# ds1804.net
KiCad netlist of a schematic drawn in EAGLE
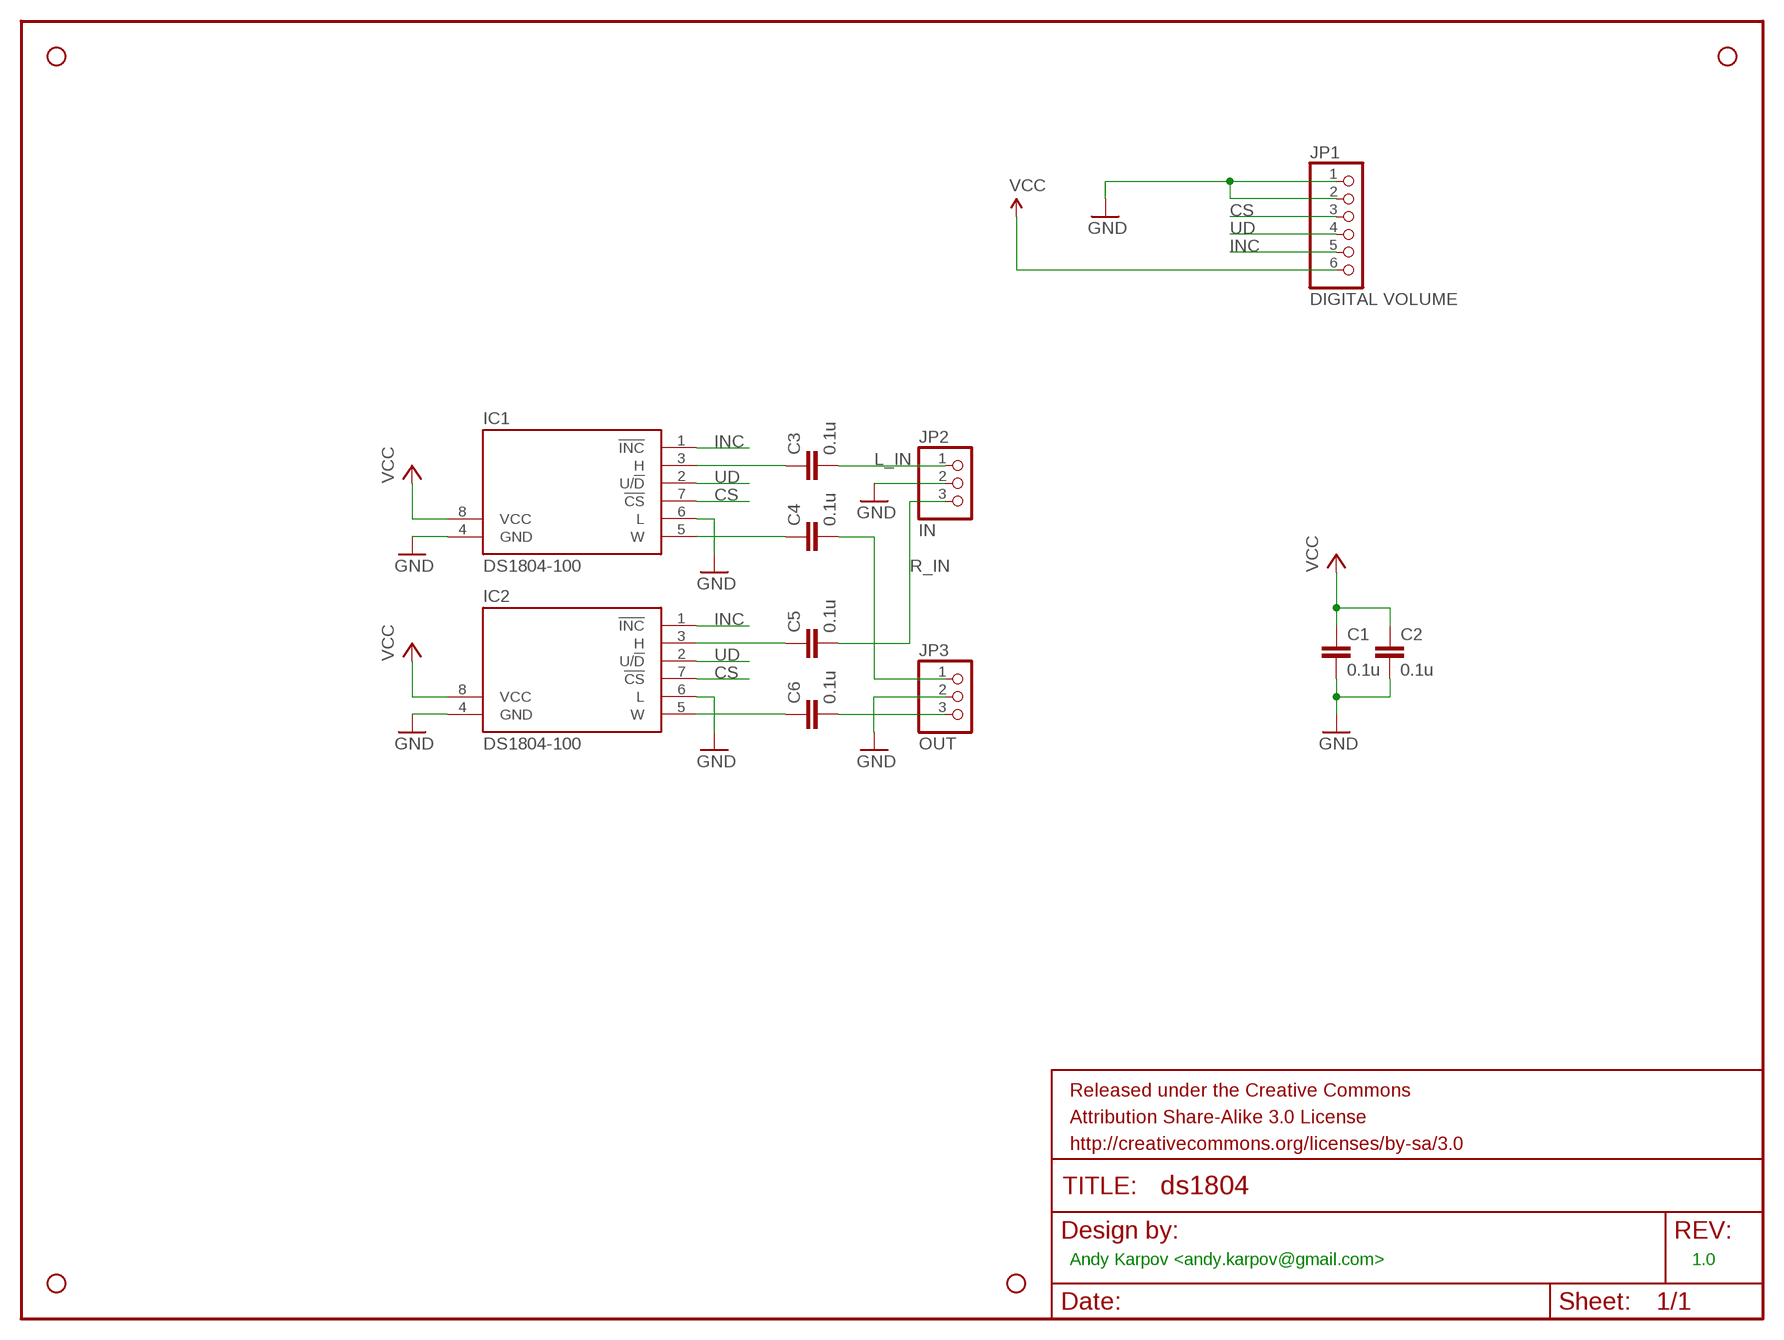
[diagram p0: schematic, sheet 1]

(export (version "E")
  (design (tool "Eeschema 10.0.6"))
  (components
    (comp (ref "C1")
      (value "0.1u")
      (footprint "eagle-import:C025-025X050")
      (libsource (lib "eagle-import") (part "C-EU025-025X050"))
    )
    (comp (ref "C2")
      (value "0.1u")
      (footprint "eagle-import:C025-025X050")
      (libsource (lib "eagle-import") (part "C-EU025-025X050"))
    )
    (comp (ref "C3")
      (value "0.1u")
      (footprint "eagle-import:C025-025X050")
      (libsource (lib "eagle-import") (part "resistor_C-EU025-025X050"))
    )
    (comp (ref "C4")
      (value "0.1u")
      (footprint "eagle-import:C025-025X050")
      (libsource (lib "eagle-import") (part "resistor_C-EU025-025X050"))
    )
    (comp (ref "C5")
      (value "0.1u")
      (footprint "eagle-import:C025-025X050")
      (libsource (lib "eagle-import") (part "resistor_C-EU025-025X050"))
    )
    (comp (ref "C6")
      (value "0.1u")
      (footprint "eagle-import:C025-025X050")
      (libsource (lib "eagle-import") (part "resistor_C-EU025-025X050"))
    )
    (comp (ref "FRAME1")
      (value "FRAME-LETTER")
      (footprint "eagle-import:CREATIVE_COMMONS")
      (libsource (lib "eagle-import") (part "FRAME-LETTER"))
    )
    (comp (ref "IC1")
      (value "DS1804-100")
      (footprint "eagle-import:DIL08")
      (libsource (lib "eagle-import") (part "DS1804P"))
    )
    (comp (ref "IC2")
      (value "DS1804-100")
      (footprint "eagle-import:DIL08")
      (libsource (lib "eagle-import") (part "DS1804P"))
    )
    (comp (ref "JP1")
      (value "DIGITAL VOLUME")
      (footprint "eagle-import:1X06")
      (libsource (lib "eagle-import") (part "PINHD-1X6"))
    )
    (comp (ref "JP2")
      (value "IN")
      (footprint "eagle-import:1X03")
      (libsource (lib "eagle-import") (part "PINHD-1X3"))
    )
    (comp (ref "JP3")
      (value "OUT")
      (footprint "eagle-import:1X03")
      (libsource (lib "eagle-import") (part "PINHD-1X3"))
    )
    (comp (ref "STANDOFF1")
      (value "STAND-OFF")
      (footprint "eagle-import:STAND-OFF")
      (libsource (lib "eagle-import") (part "STAND-OFF"))
    )
    (comp (ref "STANDOFF2")
      (value "STAND-OFF")
      (footprint "eagle-import:STAND-OFF")
      (libsource (lib "eagle-import") (part "STAND-OFF"))
    )
    (comp (ref "STANDOFF3")
      (value "STAND-OFF")
      (footprint "eagle-import:STAND-OFF")
      (libsource (lib "eagle-import") (part "STAND-OFF"))
    )
    (comp (ref "STANDOFF4")
      (value "STAND-OFF")
      (footprint "eagle-import:STAND-OFF")
      (libsource (lib "eagle-import") (part "STAND-OFF"))
    )
  )
  (nets
    (net (code "1") (name "/CS") (class "Default")
      (node (ref "IC1") (pin "7") (pinfunction "~{CS}_7") (pintype "bidirectional"))
      (node (ref "IC2") (pin "7") (pinfunction "~{CS}_7") (pintype "bidirectional"))
      (node (ref "JP1") (pin "3") (pinfunction "3_3") (pintype "passive"))
    )
    (net (code "2") (name "/INC") (class "Default")
      (node (ref "IC1") (pin "1") (pinfunction "~{INC}_1") (pintype "bidirectional"))
      (node (ref "IC2") (pin "1") (pinfunction "~{INC}_1") (pintype "bidirectional"))
      (node (ref "JP1") (pin "5") (pinfunction "5_5") (pintype "passive"))
    )
    (net (code "3") (name "/L_IN") (class "Default")
      (node (ref "C3") (pin "2") (pinfunction "2_2") (pintype "passive"))
      (node (ref "JP2") (pin "1") (pinfunction "1_1") (pintype "passive"))
    )
    (net (code "4") (name "/R_IN") (class "Default")
      (node (ref "C5") (pin "2") (pinfunction "2_2") (pintype "passive"))
      (node (ref "JP2") (pin "3") (pinfunction "3_3") (pintype "passive"))
    )
    (net (code "5") (name "/UD") (class "Default")
      (node (ref "IC1") (pin "2") (pinfunction "U/~{D}_2") (pintype "bidirectional"))
      (node (ref "IC2") (pin "2") (pinfunction "U/~{D}_2") (pintype "bidirectional"))
      (node (ref "JP1") (pin "4") (pinfunction "4_4") (pintype "passive"))
    )
    (net (code "6") (name "GND") (class "Default")
      (node (ref "C1") (pin "2") (pinfunction "2_2") (pintype "passive"))
      (node (ref "C2") (pin "2") (pinfunction "2_2") (pintype "passive"))
      (node (ref "IC1") (pin "4") (pinfunction "GND_4") (pintype "power_in"))
      (node (ref "IC1") (pin "6") (pinfunction "L_6") (pintype "bidirectional"))
      (node (ref "IC2") (pin "4") (pinfunction "GND_4") (pintype "power_in"))
      (node (ref "IC2") (pin "6") (pinfunction "L_6") (pintype "bidirectional"))
      (node (ref "JP1") (pin "1") (pinfunction "1_1") (pintype "passive"))
      (node (ref "JP1") (pin "2") (pinfunction "2_2") (pintype "passive"))
      (node (ref "JP2") (pin "2") (pinfunction "2_2") (pintype "passive"))
      (node (ref "JP3") (pin "2") (pinfunction "2_2") (pintype "passive"))
    )
    (net (code "7") (name "Net-(C4-Pad2)") (class "Default")
      (node (ref "C4") (pin "2") (pinfunction "2_2") (pintype "passive"))
      (node (ref "JP3") (pin "1") (pinfunction "1_1") (pintype "passive"))
    )
    (net (code "8") (name "Net-(C6-Pad2)") (class "Default")
      (node (ref "C6") (pin "2") (pinfunction "2_2") (pintype "passive"))
      (node (ref "JP3") (pin "3") (pinfunction "3_3") (pintype "passive"))
    )
    (net (code "9") (name "Net-(IC1-H)") (class "Default")
      (node (ref "C3") (pin "1") (pinfunction "1_1") (pintype "passive"))
      (node (ref "IC1") (pin "3") (pinfunction "H_3") (pintype "bidirectional"))
    )
    (net (code "10") (name "Net-(IC1-W)") (class "Default")
      (node (ref "C4") (pin "1") (pinfunction "1_1") (pintype "passive"))
      (node (ref "IC1") (pin "5") (pinfunction "W_5") (pintype "bidirectional"))
    )
    (net (code "11") (name "Net-(IC2-H)") (class "Default")
      (node (ref "C5") (pin "1") (pinfunction "1_1") (pintype "passive"))
      (node (ref "IC2") (pin "3") (pinfunction "H_3") (pintype "bidirectional"))
    )
    (net (code "12") (name "Net-(IC2-W)") (class "Default")
      (node (ref "C6") (pin "1") (pinfunction "1_1") (pintype "passive"))
      (node (ref "IC2") (pin "5") (pinfunction "W_5") (pintype "bidirectional"))
    )
    (net (code "13") (name "VCC") (class "Default")
      (node (ref "C1") (pin "1") (pinfunction "1_1") (pintype "passive"))
      (node (ref "C2") (pin "1") (pinfunction "1_1") (pintype "passive"))
      (node (ref "IC1") (pin "8") (pinfunction "VCC_8") (pintype "power_in"))
      (node (ref "IC2") (pin "8") (pinfunction "VCC_8") (pintype "power_in"))
      (node (ref "JP1") (pin "6") (pinfunction "6_6") (pintype "passive"))
    )
  )
)
